# Bus_V3_0.net
KiCad netlist of a schematic drawn in EAGLE
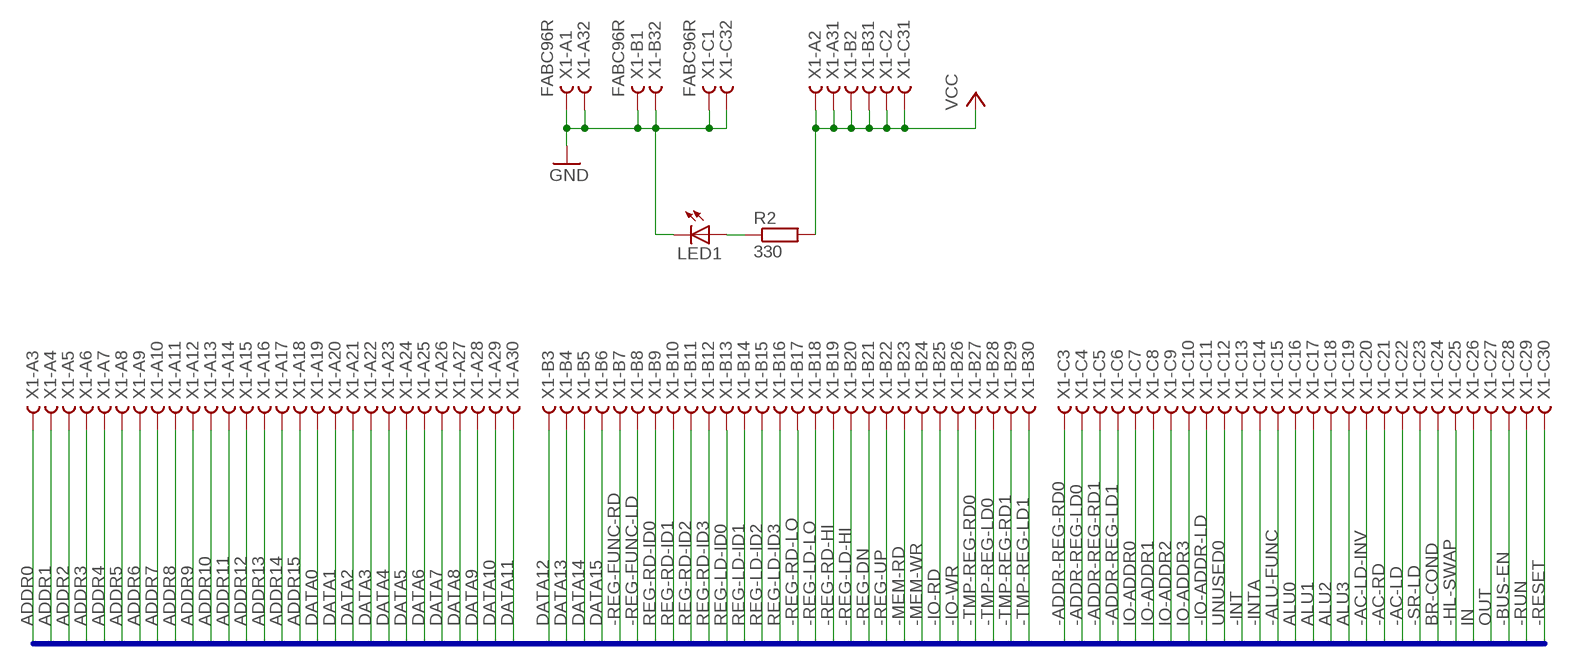
[diagram p0: schematic, sheet 1]

(export (version "E")
  (design (tool "Eeschema 10.0.6"))
  (components
    (comp (ref "LED1")
      (value "LED5MM")
      (footprint "eagle-import:LED5MM")
      (libsource (lib "eagle-import") (part "LED5MM"))
    )
    (comp (ref "R2")
      (value "330")
      (footprint "eagle-import:0207_10")
      (libsource (lib "eagle-import") (part "R0207/10"))
    )
    (comp (ref "X1")
      (value "FABC96R")
      (footprint "eagle-import:FABC96R")
      (libsource (lib "eagle-import") (part "FABC96R"))
    )
  )
  (nets
    (net (code "1") (name "/-AC-LD") (class "Default")
      (node (ref "X1") (pin "C22") (pinfunction "B_C22") (pintype "passive"))
    )
    (net (code "2") (name "/-AC-LD-INV") (class "Default")
      (node (ref "X1") (pin "C20") (pinfunction "B_C20") (pintype "passive"))
    )
    (net (code "3") (name "/-AC-RD") (class "Default")
      (node (ref "X1") (pin "C21") (pinfunction "B_C21") (pintype "passive"))
    )
    (net (code "4") (name "/-ADDR-REG-LD0") (class "Default")
      (node (ref "X1") (pin "C4") (pinfunction "B_C4") (pintype "passive"))
    )
    (net (code "5") (name "/-ADDR-REG-LD1") (class "Default")
      (node (ref "X1") (pin "C6") (pinfunction "B_C6") (pintype "passive"))
    )
    (net (code "6") (name "/-ADDR-REG-RD0") (class "Default")
      (node (ref "X1") (pin "C3") (pinfunction "B_C3") (pintype "passive"))
    )
    (net (code "7") (name "/-ADDR-REG-RD1") (class "Default")
      (node (ref "X1") (pin "C5") (pinfunction "B_C5") (pintype "passive"))
    )
    (net (code "8") (name "/-ALU-FUNC") (class "Default")
      (node (ref "X1") (pin "C15") (pinfunction "B_C15") (pintype "passive"))
    )
    (net (code "9") (name "/-BUS-EN") (class "Default")
      (node (ref "X1") (pin "C28") (pinfunction "B_C28") (pintype "passive"))
    )
    (net (code "10") (name "/-HL-SWAP") (class "Default")
      (node (ref "X1") (pin "C25") (pinfunction "B_C25") (pintype "passive"))
    )
    (net (code "11") (name "/-INT") (class "Default")
      (node (ref "X1") (pin "C13") (pinfunction "B_C13") (pintype "passive"))
    )
    (net (code "12") (name "/-INTA") (class "Default")
      (node (ref "X1") (pin "C14") (pinfunction "B_C14") (pintype "passive"))
    )
    (net (code "13") (name "/-IO-ADDR-LD") (class "Default")
      (node (ref "X1") (pin "C11") (pinfunction "B_C11") (pintype "passive"))
    )
    (net (code "14") (name "/-IO-RD") (class "Default")
      (node (ref "X1") (pin "B25") (pinfunction "B_B25") (pintype "passive"))
    )
    (net (code "15") (name "/-IO-WR") (class "Default")
      (node (ref "X1") (pin "B26") (pinfunction "B_B26") (pintype "passive"))
    )
    (net (code "16") (name "/-MEM-RD") (class "Default")
      (node (ref "X1") (pin "B23") (pinfunction "B_B23") (pintype "passive"))
    )
    (net (code "17") (name "/-MEM-WR") (class "Default")
      (node (ref "X1") (pin "B24") (pinfunction "B_B24") (pintype "passive"))
    )
    (net (code "18") (name "/-REG-DN") (class "Default")
      (node (ref "X1") (pin "B21") (pinfunction "B_B21") (pintype "passive"))
    )
    (net (code "19") (name "/-REG-FUNC-LD") (class "Default")
      (node (ref "X1") (pin "B8") (pinfunction "B_B8") (pintype "passive"))
    )
    (net (code "20") (name "/-REG-FUNC-RD") (class "Default")
      (node (ref "X1") (pin "B7") (pinfunction "B_B7") (pintype "passive"))
    )
    (net (code "21") (name "/-REG-LD-HI") (class "Default")
      (node (ref "X1") (pin "B20") (pinfunction "B_B20") (pintype "passive"))
    )
    (net (code "22") (name "/-REG-LD-LO") (class "Default")
      (node (ref "X1") (pin "B18") (pinfunction "B_B18") (pintype "passive"))
    )
    (net (code "23") (name "/-REG-RD-HI") (class "Default")
      (node (ref "X1") (pin "B19") (pinfunction "B_B19") (pintype "passive"))
    )
    (net (code "24") (name "/-REG-RD-LO") (class "Default")
      (node (ref "X1") (pin "B17") (pinfunction "B_B17") (pintype "passive"))
    )
    (net (code "25") (name "/-REG-UP") (class "Default")
      (node (ref "X1") (pin "B22") (pinfunction "B_B22") (pintype "passive"))
    )
    (net (code "26") (name "/-RESET") (class "Default")
      (node (ref "X1") (pin "C30") (pinfunction "B_C30") (pintype "passive"))
    )
    (net (code "27") (name "/-RUN") (class "Default")
      (node (ref "X1") (pin "C29") (pinfunction "B_C29") (pintype "passive"))
    )
    (net (code "28") (name "/-SR-LD") (class "Default")
      (node (ref "X1") (pin "C23") (pinfunction "B_C23") (pintype "passive"))
    )
    (net (code "29") (name "/-TMP-REG-LD0") (class "Default")
      (node (ref "X1") (pin "B28") (pinfunction "B_B28") (pintype "passive"))
    )
    (net (code "30") (name "/-TMP-REG-LD1") (class "Default")
      (node (ref "X1") (pin "B30") (pinfunction "B_B30") (pintype "passive"))
    )
    (net (code "31") (name "/-TMP-REG-RD0") (class "Default")
      (node (ref "X1") (pin "B27") (pinfunction "B_B27") (pintype "passive"))
    )
    (net (code "32") (name "/-TMP-REG-RD1") (class "Default")
      (node (ref "X1") (pin "B29") (pinfunction "B_B29") (pintype "passive"))
    )
    (net (code "33") (name "/ADDR0") (class "Default")
      (node (ref "X1") (pin "A3") (pinfunction "B_A3") (pintype "passive"))
    )
    (net (code "34") (name "/ADDR1") (class "Default")
      (node (ref "X1") (pin "A4") (pinfunction "B_A4") (pintype "passive"))
    )
    (net (code "35") (name "/ADDR2") (class "Default")
      (node (ref "X1") (pin "A5") (pinfunction "B_A5") (pintype "passive"))
    )
    (net (code "36") (name "/ADDR3") (class "Default")
      (node (ref "X1") (pin "A6") (pinfunction "B_A6") (pintype "passive"))
    )
    (net (code "37") (name "/ADDR4") (class "Default")
      (node (ref "X1") (pin "A7") (pinfunction "B_A7") (pintype "passive"))
    )
    (net (code "38") (name "/ADDR5") (class "Default")
      (node (ref "X1") (pin "A8") (pinfunction "B_A8") (pintype "passive"))
    )
    (net (code "39") (name "/ADDR6") (class "Default")
      (node (ref "X1") (pin "A9") (pinfunction "B_A9") (pintype "passive"))
    )
    (net (code "40") (name "/ADDR7") (class "Default")
      (node (ref "X1") (pin "A10") (pinfunction "B_A10") (pintype "passive"))
    )
    (net (code "41") (name "/ADDR8") (class "Default")
      (node (ref "X1") (pin "A11") (pinfunction "B_A11") (pintype "passive"))
    )
    (net (code "42") (name "/ADDR9") (class "Default")
      (node (ref "X1") (pin "A12") (pinfunction "B_A12") (pintype "passive"))
    )
    (net (code "43") (name "/ADDR10") (class "Default")
      (node (ref "X1") (pin "A13") (pinfunction "B_A13") (pintype "passive"))
    )
    (net (code "44") (name "/ADDR11") (class "Default")
      (node (ref "X1") (pin "A14") (pinfunction "B_A14") (pintype "passive"))
    )
    (net (code "45") (name "/ADDR12") (class "Default")
      (node (ref "X1") (pin "A15") (pinfunction "B_A15") (pintype "passive"))
    )
    (net (code "46") (name "/ADDR13") (class "Default")
      (node (ref "X1") (pin "A16") (pinfunction "B_A16") (pintype "passive"))
    )
    (net (code "47") (name "/ADDR14") (class "Default")
      (node (ref "X1") (pin "A17") (pinfunction "B_A17") (pintype "passive"))
    )
    (net (code "48") (name "/ADDR15") (class "Default")
      (node (ref "X1") (pin "A18") (pinfunction "B_A18") (pintype "passive"))
    )
    (net (code "49") (name "/ALU0") (class "Default")
      (node (ref "X1") (pin "C16") (pinfunction "B_C16") (pintype "passive"))
    )
    (net (code "50") (name "/ALU1") (class "Default")
      (node (ref "X1") (pin "C17") (pinfunction "B_C17") (pintype "passive"))
    )
    (net (code "51") (name "/ALU2") (class "Default")
      (node (ref "X1") (pin "C18") (pinfunction "B_C18") (pintype "passive"))
    )
    (net (code "52") (name "/ALU3") (class "Default")
      (node (ref "X1") (pin "C19") (pinfunction "B_C19") (pintype "passive"))
    )
    (net (code "53") (name "/BR-COND") (class "Default")
      (node (ref "X1") (pin "C24") (pinfunction "B_C24") (pintype "passive"))
    )
    (net (code "54") (name "/DATA0") (class "Default")
      (node (ref "X1") (pin "A19") (pinfunction "B_A19") (pintype "passive"))
    )
    (net (code "55") (name "/DATA1") (class "Default")
      (node (ref "X1") (pin "A20") (pinfunction "B_A20") (pintype "passive"))
    )
    (net (code "56") (name "/DATA2") (class "Default")
      (node (ref "X1") (pin "A21") (pinfunction "B_A21") (pintype "passive"))
    )
    (net (code "57") (name "/DATA3") (class "Default")
      (node (ref "X1") (pin "A22") (pinfunction "B_A22") (pintype "passive"))
    )
    (net (code "58") (name "/DATA4") (class "Default")
      (node (ref "X1") (pin "A23") (pinfunction "B_A23") (pintype "passive"))
    )
    (net (code "59") (name "/DATA5") (class "Default")
      (node (ref "X1") (pin "A24") (pinfunction "B_A24") (pintype "passive"))
    )
    (net (code "60") (name "/DATA6") (class "Default")
      (node (ref "X1") (pin "A25") (pinfunction "B_A25") (pintype "passive"))
    )
    (net (code "61") (name "/DATA7") (class "Default")
      (node (ref "X1") (pin "A26") (pinfunction "B_A26") (pintype "passive"))
    )
    (net (code "62") (name "/DATA8") (class "Default")
      (node (ref "X1") (pin "A27") (pinfunction "B_A27") (pintype "passive"))
    )
    (net (code "63") (name "/DATA9") (class "Default")
      (node (ref "X1") (pin "A28") (pinfunction "B_A28") (pintype "passive"))
    )
    (net (code "64") (name "/DATA10") (class "Default")
      (node (ref "X1") (pin "A29") (pinfunction "B_A29") (pintype "passive"))
    )
    (net (code "65") (name "/DATA11") (class "Default")
      (node (ref "X1") (pin "A30") (pinfunction "B_A30") (pintype "passive"))
    )
    (net (code "66") (name "/DATA12") (class "Default")
      (node (ref "X1") (pin "B3") (pinfunction "B_B3") (pintype "passive"))
    )
    (net (code "67") (name "/DATA13") (class "Default")
      (node (ref "X1") (pin "B4") (pinfunction "B_B4") (pintype "passive"))
    )
    (net (code "68") (name "/DATA14") (class "Default")
      (node (ref "X1") (pin "B5") (pinfunction "B_B5") (pintype "passive"))
    )
    (net (code "69") (name "/DATA15") (class "Default")
      (node (ref "X1") (pin "B6") (pinfunction "B_B6") (pintype "passive"))
    )
    (net (code "70") (name "/IN") (class "Default")
      (node (ref "X1") (pin "C26") (pinfunction "B_C26") (pintype "passive"))
    )
    (net (code "71") (name "/IO-ADDR0") (class "Default")
      (node (ref "X1") (pin "C7") (pinfunction "B_C7") (pintype "passive"))
    )
    (net (code "72") (name "/IO-ADDR1") (class "Default")
      (node (ref "X1") (pin "C8") (pinfunction "B_C8") (pintype "passive"))
    )
    (net (code "73") (name "/IO-ADDR2") (class "Default")
      (node (ref "X1") (pin "C9") (pinfunction "B_C9") (pintype "passive"))
    )
    (net (code "74") (name "/IO-ADDR3") (class "Default")
      (node (ref "X1") (pin "C10") (pinfunction "B_C10") (pintype "passive"))
    )
    (net (code "75") (name "/OUT") (class "Default")
      (node (ref "X1") (pin "C27") (pinfunction "B_C27") (pintype "passive"))
    )
    (net (code "76") (name "/REG-LD-ID0") (class "Default")
      (node (ref "X1") (pin "B13") (pinfunction "B_B13") (pintype "passive"))
    )
    (net (code "77") (name "/REG-LD-ID1") (class "Default")
      (node (ref "X1") (pin "B14") (pinfunction "B_B14") (pintype "passive"))
    )
    (net (code "78") (name "/REG-LD-ID2") (class "Default")
      (node (ref "X1") (pin "B15") (pinfunction "B_B15") (pintype "passive"))
    )
    (net (code "79") (name "/REG-LD-ID3") (class "Default")
      (node (ref "X1") (pin "B16") (pinfunction "B_B16") (pintype "passive"))
    )
    (net (code "80") (name "/REG-RD-ID0") (class "Default")
      (node (ref "X1") (pin "B9") (pinfunction "B_B9") (pintype "passive"))
    )
    (net (code "81") (name "/REG-RD-ID1") (class "Default")
      (node (ref "X1") (pin "B10") (pinfunction "B_B10") (pintype "passive"))
    )
    (net (code "82") (name "/REG-RD-ID2") (class "Default")
      (node (ref "X1") (pin "B11") (pinfunction "B_B11") (pintype "passive"))
    )
    (net (code "83") (name "/REG-RD-ID3") (class "Default")
      (node (ref "X1") (pin "B12") (pinfunction "B_B12") (pintype "passive"))
    )
    (net (code "84") (name "/UNUSED0") (class "Default")
      (node (ref "X1") (pin "C12") (pinfunction "B_C12") (pintype "passive"))
    )
    (net (code "85") (name "GND") (class "Default")
      (node (ref "LED1") (pin "K") (pinfunction "C_K") (pintype "passive"))
      (node (ref "X1") (pin "A1") (pinfunction "B_A1") (pintype "passive"))
      (node (ref "X1") (pin "A32") (pinfunction "B_A32") (pintype "passive"))
      (node (ref "X1") (pin "B1") (pinfunction "B_B1") (pintype "passive"))
      (node (ref "X1") (pin "B32") (pinfunction "B_B32") (pintype "passive"))
      (node (ref "X1") (pin "C1") (pinfunction "B_C1") (pintype "passive"))
      (node (ref "X1") (pin "C32") (pinfunction "B_C32") (pintype "passive"))
    )
    (net (code "86") (name "Net-(LED1-PadA)") (class "Default")
      (node (ref "LED1") (pin "A") (pinfunction "A_A") (pintype "passive"))
      (node (ref "R2") (pin "1") (pinfunction "1_1") (pintype "passive"))
    )
    (net (code "87") (name "VCC") (class "Default")
      (node (ref "R2") (pin "2") (pinfunction "2_2") (pintype "passive"))
      (node (ref "X1") (pin "A2") (pinfunction "B_A2") (pintype "passive"))
      (node (ref "X1") (pin "A31") (pinfunction "B_A31") (pintype "passive"))
      (node (ref "X1") (pin "B2") (pinfunction "B_B2") (pintype "passive"))
      (node (ref "X1") (pin "B31") (pinfunction "B_B31") (pintype "passive"))
      (node (ref "X1") (pin "C2") (pinfunction "B_C2") (pintype "passive"))
      (node (ref "X1") (pin "C31") (pinfunction "B_C31") (pintype "passive"))
    )
  )
)
